# can-rs232.net
KiCad netlist of a schematic drawn in Altium Designer
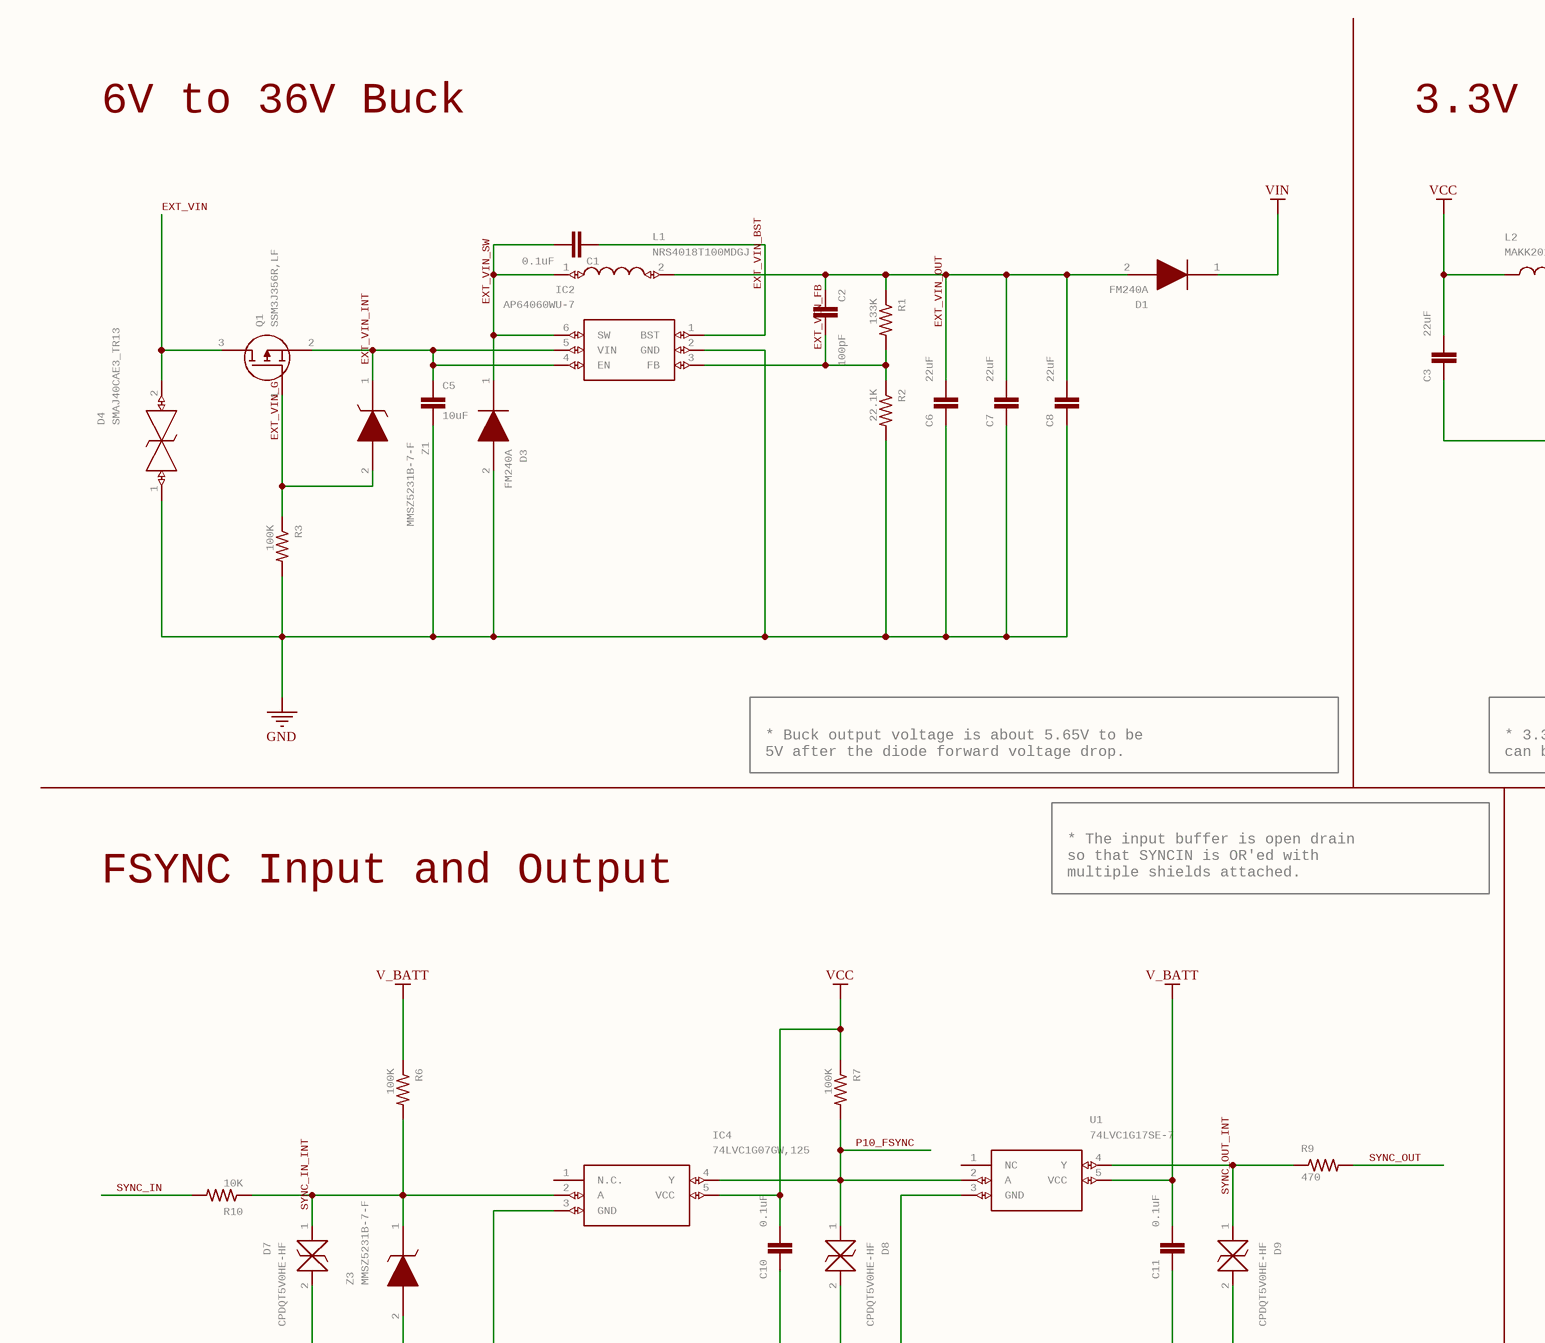
[diagram p0: can-rs232.SchDoc, top left]
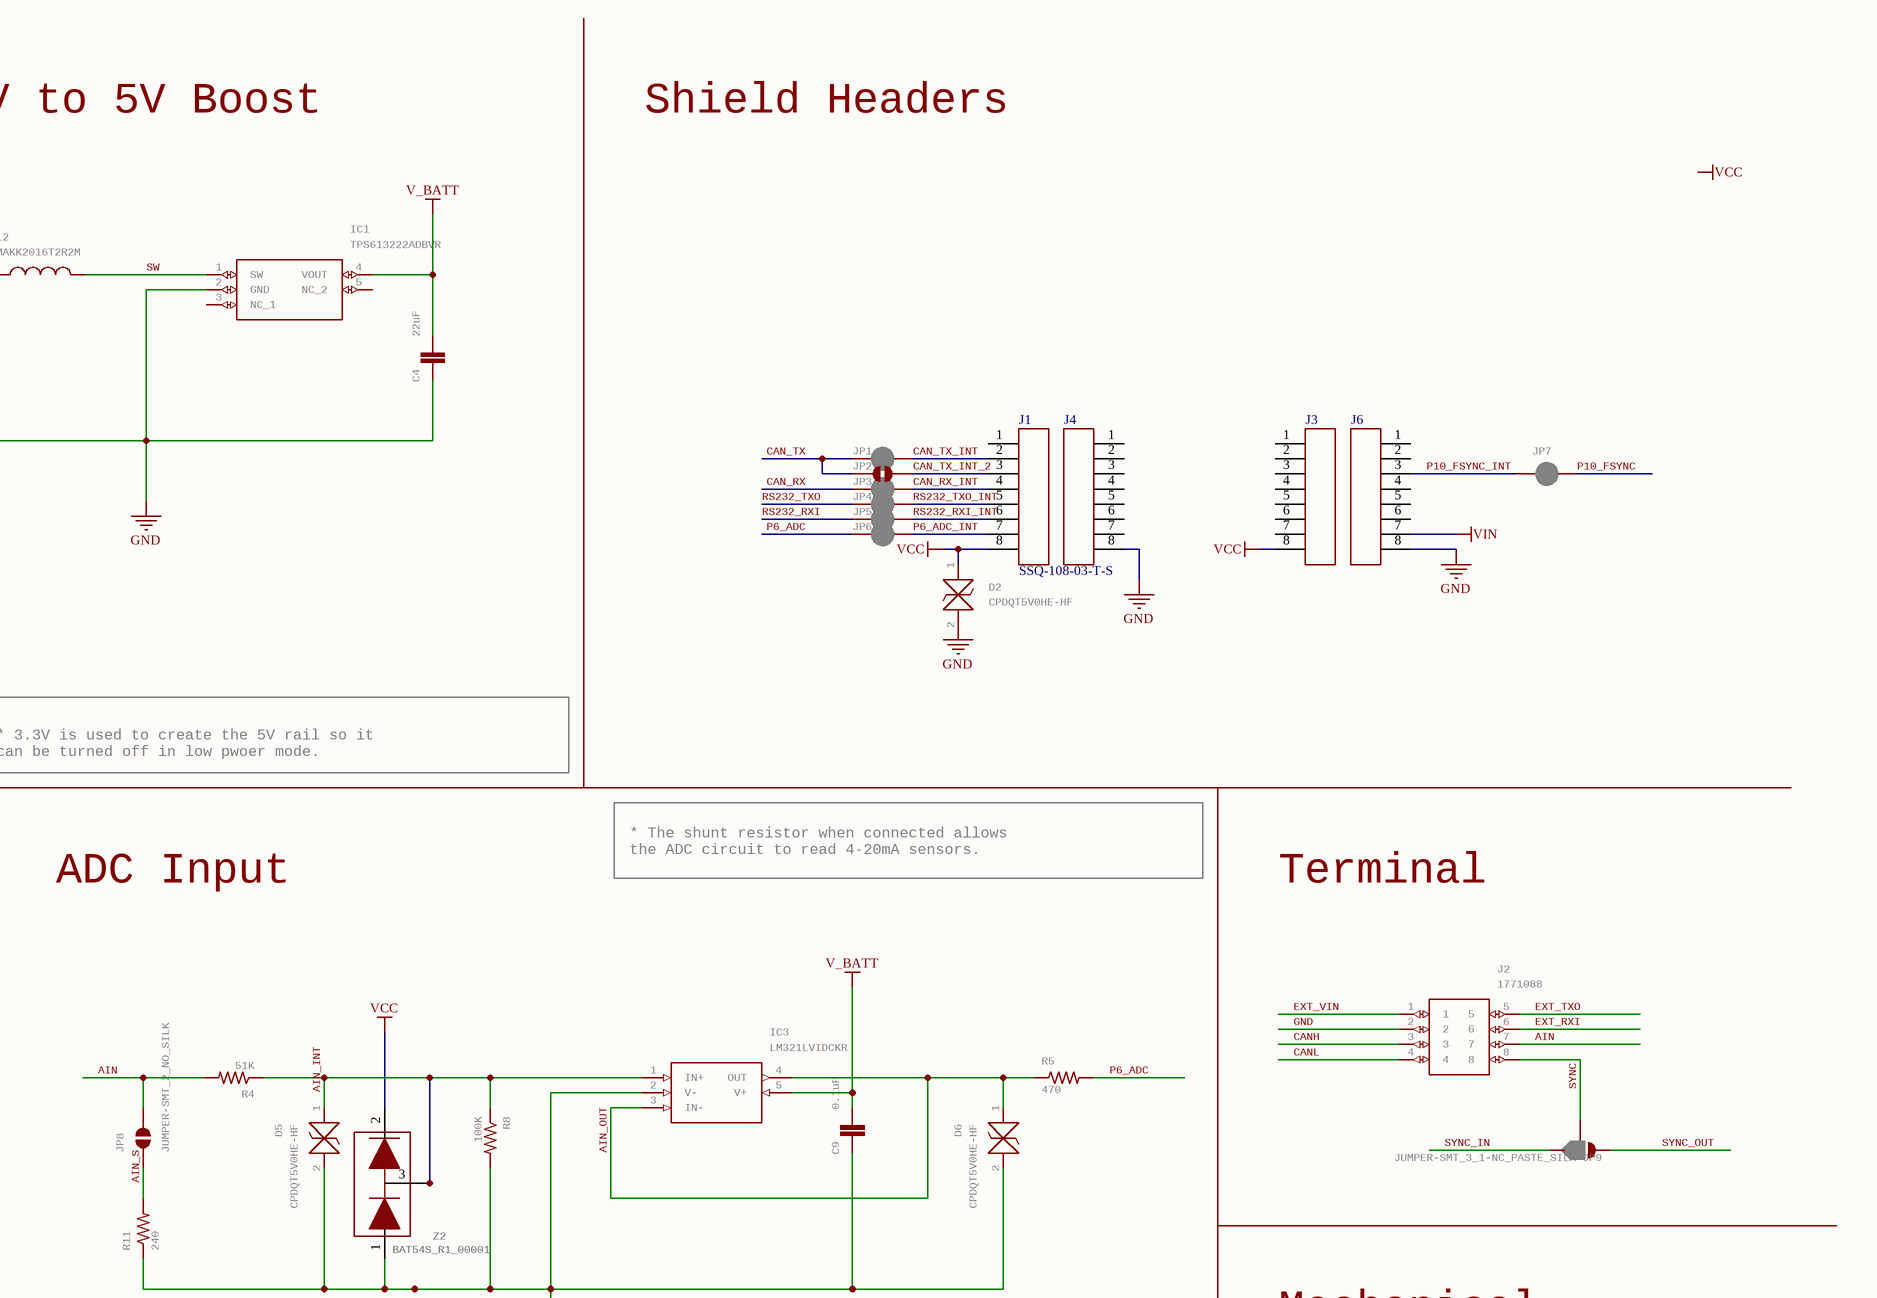
[diagram p1: can-rs232.SchDoc, top right]
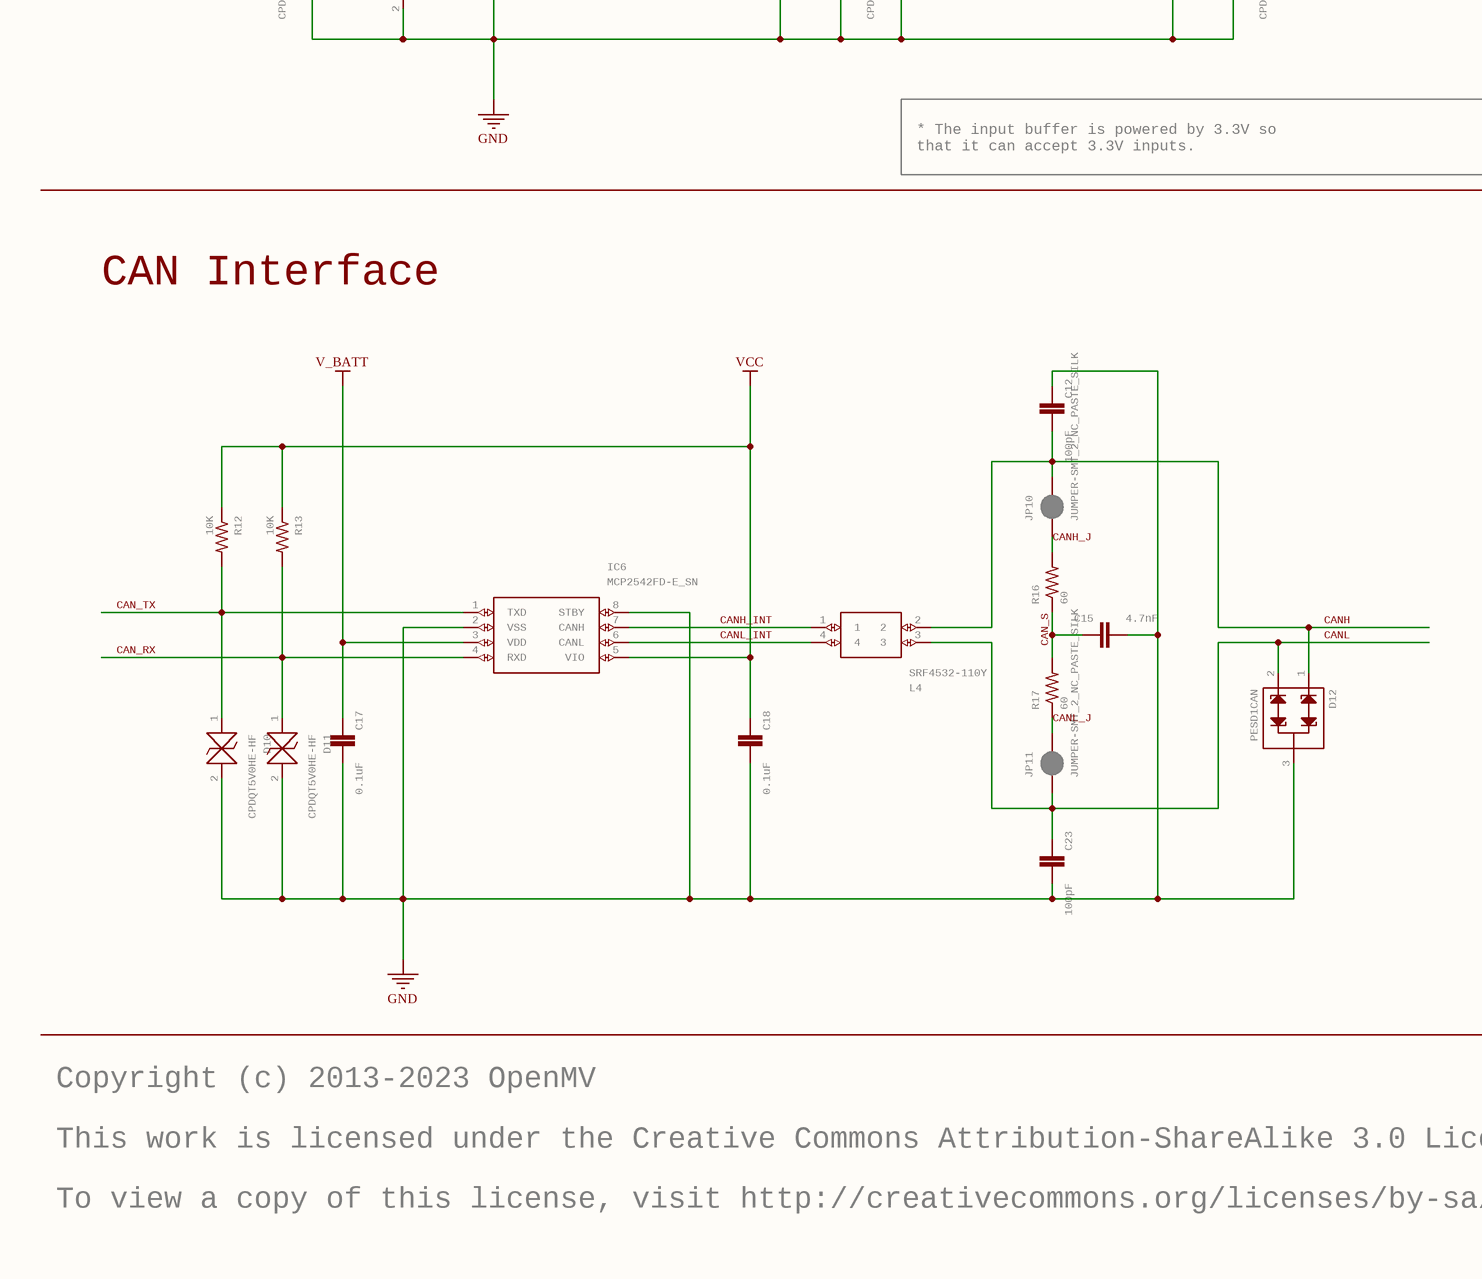
[diagram p2: can-rs232.SchDoc, bottom left]
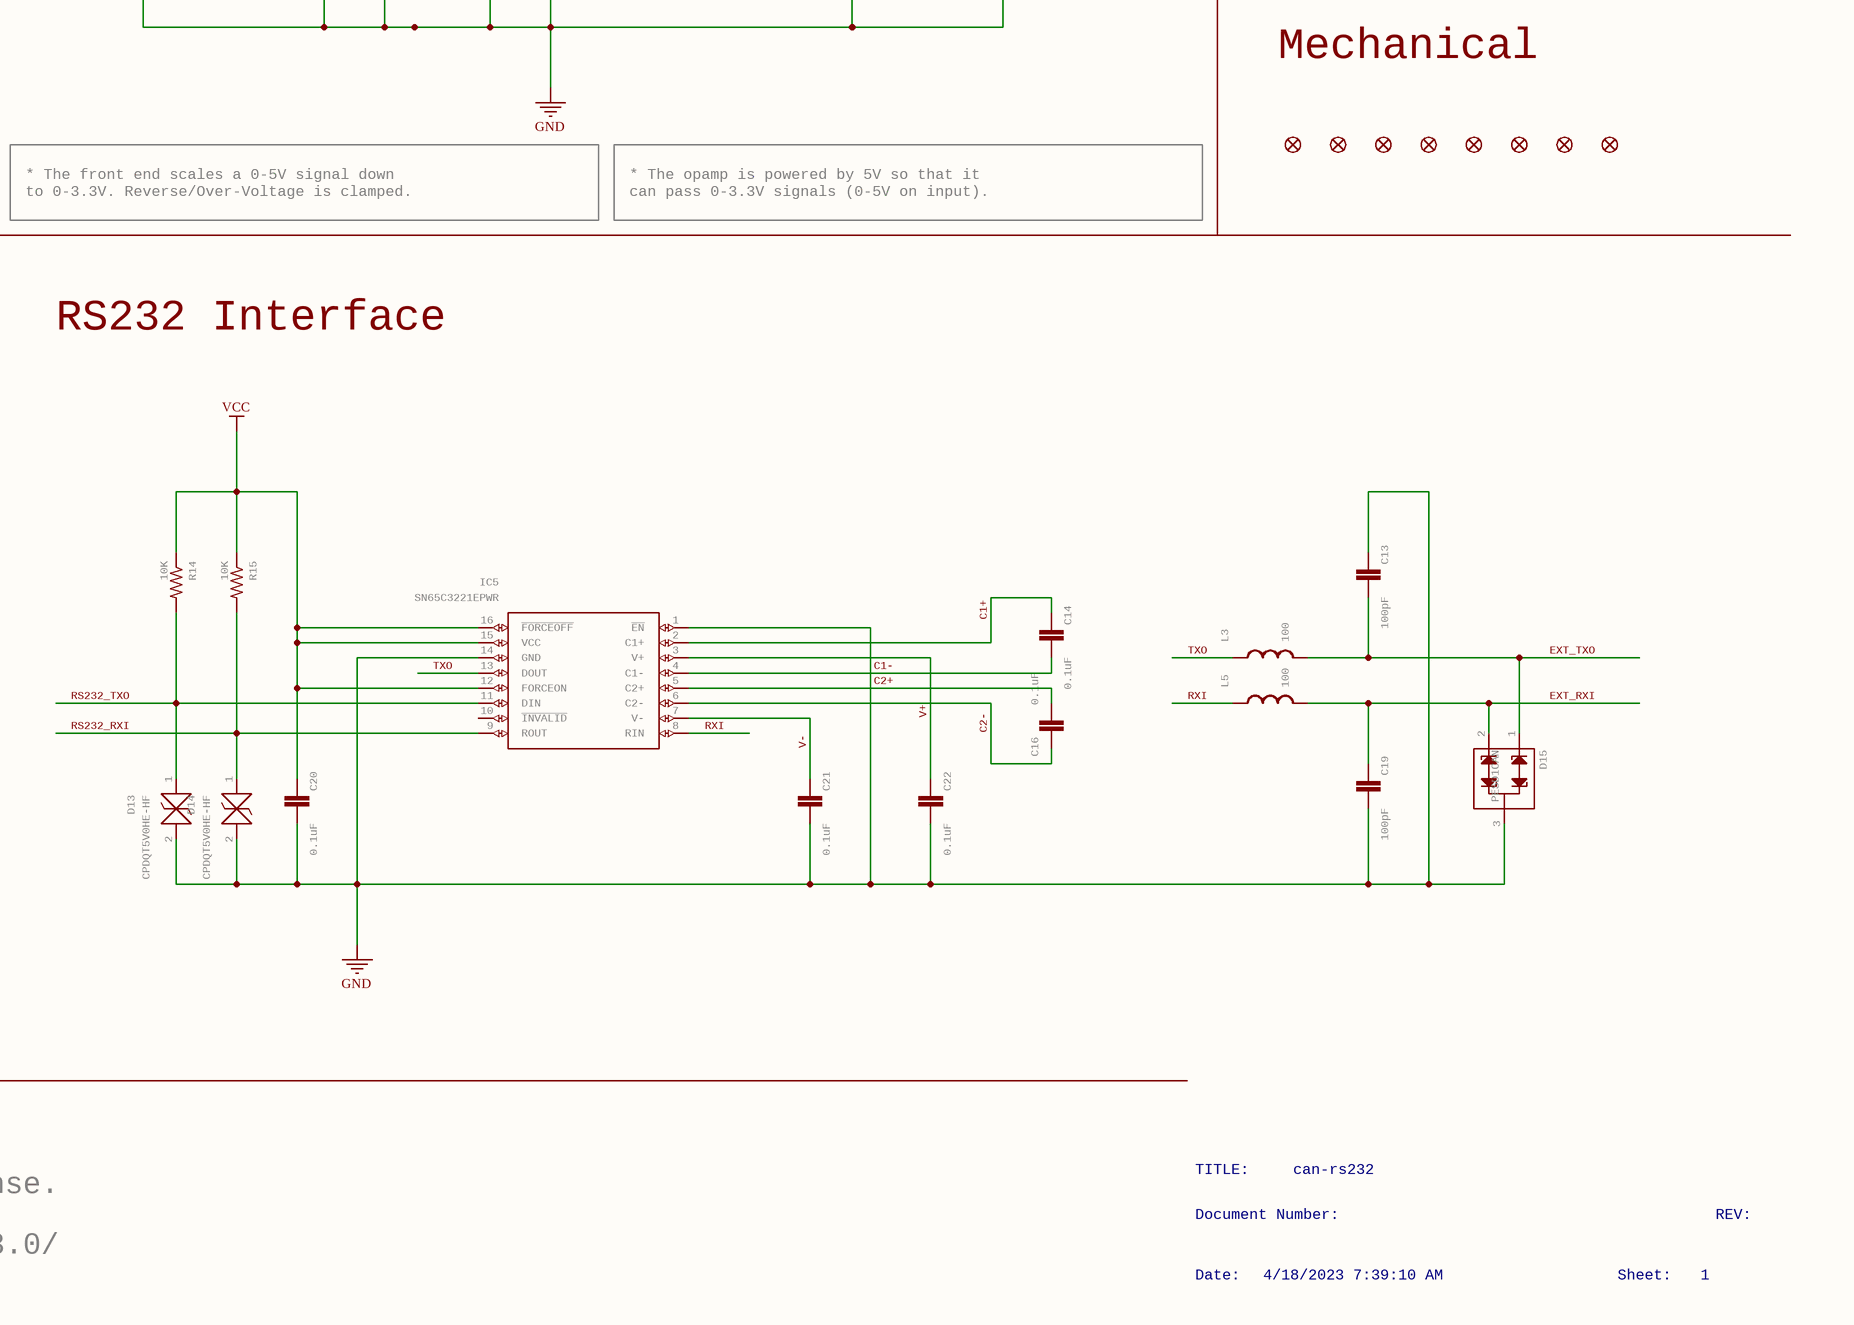
[diagram p3: can-rs232.SchDoc, bottom right]

(export (version "E")
  (design (tool "Eeschema 10.0.6"))
  (components
    (comp (ref "C1")
      (value "0.1uF")
      (footprint "0402-CAP")
      (description "CapacitorStandard 0603 ceramic capacitor, and 0.1\" leaded capacitor.")
      (fields (field (name "MPN") "GRM155R71H104KE14D"))
      (libsource (lib "") (part "CAP0402-CAP_2"))
    )
    (comp (ref "C2")
      (value "100pF")
      (footprint "0402-CAP")
      (description "CapacitorStandard 0603 ceramic capacitor, and 0.1\" leaded capacitor.")
      (fields (field (name "MPN") "CC0402JRNPO9BN101"))
      (libsource (lib "can-rs232") (part "CAP0402-CAP"))
    )
    (comp (ref "C3")
      (value "22uF")
      (footprint "0805")
      (fields (field (name "MPN") "CL21A226MQQNNNE"))
      (libsource (lib "can-rs232") (part "22UF-0805-6.3V-20%"))
    )
    (comp (ref "C4")
      (value "22uF")
      (footprint "0805")
      (fields (field (name "MPN") "CL21A226MQQNNNE"))
      (libsource (lib "can-rs232") (part "22UF-0805-6.3V-20%"))
    )
    (comp (ref "C5")
      (value "10uF")
      (footprint "C0805")
      (description "CAPACITOR, European symbol")
      (fields (field (name "MPN") "GRM21BR61H106KE43K"))
      (libsource (lib "can-rs232") (part "C-EUC0805"))
    )
    (comp (ref "C6")
      (value "22uF")
      (footprint "0805")
      (fields (field (name "MPN") "CL21A226MQQNNNE"))
      (libsource (lib "can-rs232") (part "22UF-0805-6.3V-20%"))
    )
    (comp (ref "C7")
      (value "22uF")
      (footprint "0805")
      (fields (field (name "MPN") "CL21A226MQQNNNE"))
      (libsource (lib "can-rs232") (part "22UF-0805-6.3V-20%"))
    )
    (comp (ref "C8")
      (value "22uF")
      (footprint "0805")
      (fields (field (name "MPN") "CL21A226MQQNNNE"))
      (libsource (lib "can-rs232") (part "22UF-0805-6.3V-20%"))
    )
    (comp (ref "C9")
      (value "0.1uF")
      (footprint "0402-CAP")
      (description "CapacitorStandard 0603 ceramic capacitor, and 0.1\" leaded capacitor.")
      (fields (field (name "MPN") "GRM155R71H104KE14D"))
      (libsource (lib "") (part "CAP0402-CAP_1"))
    )
    (comp (ref "C10")
      (value "0.1uF")
      (footprint "0402-CAP")
      (description "CapacitorStandard 0603 ceramic capacitor, and 0.1\" leaded capacitor.")
      (fields (field (name "MPN") "GRM155R71H104KE14D"))
      (libsource (lib "") (part "CAP0402-CAP_1"))
    )
    (comp (ref "C11")
      (value "0.1uF")
      (footprint "0402-CAP")
      (description "CapacitorStandard 0603 ceramic capacitor, and 0.1\" leaded capacitor.")
      (fields (field (name "MPN") "GRM155R71H104KE14D"))
      (libsource (lib "") (part "CAP0402-CAP_1"))
    )
    (comp (ref "C12")
      (value "100pF")
      (footprint "0402-CAP")
      (description "CapacitorStandard 0603 ceramic capacitor, and 0.1\" leaded capacitor.")
      (fields (field (name "MPN") "CC0402JRNPO9BN101"))
      (libsource (lib "can-rs232") (part "CAP0402-CAP"))
    )
    (comp (ref "C13")
      (value "100pF")
      (footprint "0402-CAP")
      (description "CapacitorStandard 0603 ceramic capacitor, and 0.1\" leaded capacitor.")
      (fields (field (name "MPN") "CC0402JRNPO9BN101"))
      (libsource (lib "can-rs232") (part "CAP0402-CAP"))
    )
    (comp (ref "C14")
      (value "0.1uF")
      (footprint "0402-CAP")
      (description "CapacitorStandard 0603 ceramic capacitor, and 0.1\" leaded capacitor.")
      (fields (field (name "MPN") "GRM155R71H104KE14D"))
      (libsource (lib "can-rs232") (part "CAP0402-CAP"))
    )
    (comp (ref "C15")
      (value "4.7nF")
      (footprint "0402-CAP")
      (description "CapacitorStandard 0603 ceramic capacitor, and 0.1\" leaded capacitor.")
      (fields (field (name "MPN") "GRM155R71H472JA01D"))
      (libsource (lib "") (part "CAP0402-CAP_3"))
    )
    (comp (ref "C16")
      (value "0.1uF")
      (footprint "0402-CAP")
      (description "CapacitorStandard 0603 ceramic capacitor, and 0.1\" leaded capacitor.")
      (fields (field (name "MPN") "GRM155R71H104KE14D"))
      (libsource (lib "") (part "CAP0402-CAP_1"))
    )
    (comp (ref "C17")
      (value "0.1uF")
      (footprint "0402-CAP")
      (description "CapacitorStandard 0603 ceramic capacitor, and 0.1\" leaded capacitor.")
      (fields (field (name "MPN") "GRM155R71H104KE14D"))
      (libsource (lib "can-rs232") (part "CAP0402-CAP"))
    )
    (comp (ref "C18")
      (value "0.1uF")
      (footprint "0402-CAP")
      (description "CapacitorStandard 0603 ceramic capacitor, and 0.1\" leaded capacitor.")
      (fields (field (name "MPN") "GRM155R71H104KE14D"))
      (libsource (lib "can-rs232") (part "CAP0402-CAP"))
    )
    (comp (ref "C19")
      (value "100pF")
      (footprint "0402-CAP")
      (description "CapacitorStandard 0603 ceramic capacitor, and 0.1\" leaded capacitor.")
      (fields (field (name "MPN") "CC0402JRNPO9BN101"))
      (libsource (lib "can-rs232") (part "CAP0402-CAP"))
    )
    (comp (ref "C20")
      (value "0.1uF")
      (footprint "0402-CAP")
      (description "CapacitorStandard 0603 ceramic capacitor, and 0.1\" leaded capacitor.")
      (fields (field (name "MPN") "GRM155R71H104KE14D"))
      (libsource (lib "can-rs232") (part "CAP0402-CAP"))
    )
    (comp (ref "C21")
      (value "0.1uF")
      (footprint "0402-CAP")
      (description "CapacitorStandard 0603 ceramic capacitor, and 0.1\" leaded capacitor.")
      (fields (field (name "MPN") "GRM155R71H104KE14D"))
      (libsource (lib "can-rs232") (part "CAP0402-CAP"))
    )
    (comp (ref "C22")
      (value "0.1uF")
      (footprint "0402-CAP")
      (description "CapacitorStandard 0603 ceramic capacitor, and 0.1\" leaded capacitor.")
      (fields (field (name "MPN") "GRM155R71H104KE14D"))
      (libsource (lib "can-rs232") (part "CAP0402-CAP"))
    )
    (comp (ref "C23")
      (value "100pF")
      (footprint "0402-CAP")
      (description "CapacitorStandard 0603 ceramic capacitor, and 0.1\" leaded capacitor.")
      (fields (field (name "MPN") "CC0402JRNPO9BN101"))
      (libsource (lib "can-rs232") (part "CAP0402-CAP"))
    )
    (comp (ref "D1")
      (value "FM240A")
      (footprint "DIOM5025X231N")
      (description "Diodes - General Purpose, Power, Switching GP Si Rectifier SMB,2A,40V   Source:  Datasheet")
      (fields (field (name "MOUSER_PART_NUMBER") "583-FM240A"))
      (libsource (lib "can-rs232") (part "FM240A"))
    )
    (comp (ref "D2")
      (value "CPDQT5V0HE-HF")
      (footprint "CPDQT5V0HEHF")
      (description "ESD Suppressors / TVS Diodes DIODE ESD 5VWM 65W 0402/SOD-923F   Source:  Datasheet")
      (fields (field (name "MOUSER_PART_NUMBER") "MOUSER_PART_NUMBER"))
      (libsource (lib "can-rs232") (part "CPDQT5V0HE-HF"))
    )
    (comp (ref "D3")
      (value "FM240A")
      (footprint "DIOM5025X231N")
      (description "Diodes - General Purpose, Power, Switching GP Si Rectifier SMB,2A,40V   Source:  Datasheet")
      (fields (field (name "MOUSER_PART_NUMBER") "583-FM240A"))
      (libsource (lib "can-rs232") (part "FM240A"))
    )
    (comp (ref "D4")
      (value "SMAJ40CAE3_TR13")
      (footprint "SMAJ40CAE3TR13")
      (description "ESD Suppressors / TVS Diodes TVS   Source:  Datasheet")
      (fields
        (field (name "MANUFACTURER_PART_NUMBER") "SMAJ40CAe3/TR13")
        (field (name "MOUSER_PART_NUMBER") "494-SMAJ40CAE3/TR13")
      )
      (libsource (lib "can-rs232") (part "SMAJ40CAE3_TR13"))
    )
    (comp (ref "D5")
      (value "CPDQT5V0HE-HF")
      (footprint "CPDQT5V0HEHF")
      (description "ESD Suppressors / TVS Diodes DIODE ESD 5VWM 65W 0402/SOD-923F   Source:  Datasheet")
      (fields (field (name "MOUSER_PART_NUMBER") "MOUSER_PART_NUMBER"))
      (libsource (lib "can-rs232") (part "CPDQT5V0HE-HF"))
    )
    (comp (ref "D6")
      (value "CPDQT5V0HE-HF")
      (footprint "CPDQT5V0HEHF")
      (description "ESD Suppressors / TVS Diodes DIODE ESD 5VWM 65W 0402/SOD-923F   Source:  Datasheet")
      (fields (field (name "MOUSER_PART_NUMBER") "MOUSER_PART_NUMBER"))
      (libsource (lib "can-rs232") (part "CPDQT5V0HE-HF"))
    )
    (comp (ref "D7")
      (value "CPDQT5V0HE-HF")
      (footprint "CPDQT5V0HEHF")
      (description "ESD Suppressors / TVS Diodes DIODE ESD 5VWM 65W 0402/SOD-923F   Source:  Datasheet")
      (fields (field (name "MOUSER_PART_NUMBER") "MOUSER_PART_NUMBER"))
      (libsource (lib "can-rs232") (part "CPDQT5V0HE-HF"))
    )
    (comp (ref "D8")
      (value "CPDQT5V0HE-HF")
      (footprint "CPDQT5V0HEHF")
      (description "ESD Suppressors / TVS Diodes DIODE ESD 5VWM 65W 0402/SOD-923F   Source:  Datasheet")
      (fields (field (name "MOUSER_PART_NUMBER") "MOUSER_PART_NUMBER"))
      (libsource (lib "can-rs232") (part "CPDQT5V0HE-HF"))
    )
    (comp (ref "D9")
      (value "CPDQT5V0HE-HF")
      (footprint "CPDQT5V0HEHF")
      (description "ESD Suppressors / TVS Diodes DIODE ESD 5VWM 65W 0402/SOD-923F   Source:  Datasheet")
      (fields (field (name "MOUSER_PART_NUMBER") "MOUSER_PART_NUMBER"))
      (libsource (lib "can-rs232") (part "CPDQT5V0HE-HF"))
    )
    (comp (ref "D10")
      (value "CPDQT5V0HE-HF")
      (footprint "CPDQT5V0HEHF")
      (description "ESD Suppressors / TVS Diodes DIODE ESD 5VWM 65W 0402/SOD-923F   Source:  Datasheet")
      (fields (field (name "MOUSER_PART_NUMBER") "MOUSER_PART_NUMBER"))
      (libsource (lib "can-rs232") (part "CPDQT5V0HE-HF"))
    )
    (comp (ref "D11")
      (value "CPDQT5V0HE-HF")
      (footprint "CPDQT5V0HEHF")
      (description "ESD Suppressors / TVS Diodes DIODE ESD 5VWM 65W 0402/SOD-923F   Source:  Datasheet")
      (fields (field (name "MOUSER_PART_NUMBER") "MOUSER_PART_NUMBER"))
      (libsource (lib "can-rs232") (part "CPDQT5V0HE-HF"))
    )
    (comp (ref "D12")
      (value "PESD1CAN")
      (footprint "SOT23-3")
      (fields (field (name "MPN") "VCAN36A2-03S-E3-08"))
      (libsource (lib "can-rs232") (part "PESD1CAN"))
    )
    (comp (ref "D13")
      (value "CPDQT5V0HE-HF")
      (footprint "CPDQT5V0HEHF")
      (description "ESD Suppressors / TVS Diodes DIODE ESD 5VWM 65W 0402/SOD-923F   Source:  Datasheet")
      (fields (field (name "MOUSER_PART_NUMBER") "MOUSER_PART_NUMBER"))
      (libsource (lib "can-rs232") (part "CPDQT5V0HE-HF"))
    )
    (comp (ref "D14")
      (value "CPDQT5V0HE-HF")
      (footprint "CPDQT5V0HEHF")
      (description "ESD Suppressors / TVS Diodes DIODE ESD 5VWM 65W 0402/SOD-923F   Source:  Datasheet")
      (fields (field (name "MOUSER_PART_NUMBER") "MOUSER_PART_NUMBER"))
      (libsource (lib "can-rs232") (part "CPDQT5V0HE-HF"))
    )
    (comp (ref "D15")
      (value "PESD1CAN")
      (footprint "SOT23-3")
      (fields (field (name "MPN") "VCAN36A2-03S-E3-08"))
      (libsource (lib "can-rs232") (part "PESD1CAN"))
    )
    (comp (ref "FD1")
      (value "FIDUCIAL1X2")
      (footprint "FIDUCIAL-1X2")
      (fields (field (name "LIBRARYNAME") "SparkFun-Aesthetics"))
      (libsource (lib "can-rs232") (part "FIDUCIAL1X2"))
    )
    (comp (ref "FD2")
      (value "FIDUCIAL1X2")
      (footprint "FIDUCIAL-1X2")
      (fields (field (name "LIBRARYNAME") "SparkFun-Aesthetics"))
      (libsource (lib "can-rs232") (part "FIDUCIAL1X2"))
    )
    (comp (ref "FD3")
      (value "FIDUCIAL1X2")
      (footprint "FIDUCIAL-1X2")
      (fields (field (name "LIBRARYNAME") "SparkFun-Aesthetics"))
      (libsource (lib "can-rs232") (part "FIDUCIAL1X2"))
    )
    (comp (ref "FD4")
      (value "FIDUCIAL1X2")
      (footprint "FIDUCIAL-1X2")
      (fields (field (name "LIBRARYNAME") "SparkFun-Aesthetics"))
      (libsource (lib "can-rs232") (part "FIDUCIAL1X2"))
    )
    (comp (ref "FD5")
      (value "FIDUCIAL1X2")
      (footprint "FIDUCIAL-1X2")
      (fields (field (name "LIBRARYNAME") "SparkFun-Aesthetics"))
      (libsource (lib "can-rs232") (part "FIDUCIAL1X2"))
    )
    (comp (ref "FD6")
      (value "FIDUCIAL1X2")
      (footprint "FIDUCIAL-1X2")
      (fields (field (name "LIBRARYNAME") "SparkFun-Aesthetics"))
      (libsource (lib "can-rs232") (part "FIDUCIAL1X2"))
    )
    (comp (ref "FD7")
      (value "FIDUCIAL1X2")
      (footprint "FIDUCIAL-1X2")
      (fields (field (name "LIBRARYNAME") "SparkFun-Aesthetics"))
      (libsource (lib "can-rs232") (part "FIDUCIAL1X2"))
    )
    (comp (ref "FD8")
      (value "FIDUCIAL1X2")
      (footprint "FIDUCIAL-1X2")
      (fields (field (name "LIBRARYNAME") "SparkFun-Aesthetics"))
      (libsource (lib "can-rs232") (part "FIDUCIAL1X2"))
    )
    (comp (ref "IC1")
      (value "TPS613222ADBVR")
      (footprint "SOT95P280X145-5N")
      (description "6-uA Quiescent Current, 1.8-A Switch Current Boost Converter   Source:  Datasheet")
      (fields (field (name "MOUSER_PART_NUMBER") "595-TPS613222ADBVR"))
      (libsource (lib "can-rs232") (part "TPS613222ADBVR"))
    )
    (comp (ref "IC2")
      (value "AP64060WU-7")
      (footprint "SOT95P280X100-6N")
      (description "Switching Voltage Regulators DCDC Conv HV Buck TSOT26(STD) T&R 3K   Source:  Datasheet")
      (fields (field (name "MOUSER_PART_NUMBER") "621-AP64060WU-7"))
      (libsource (lib "can-rs232") (part "AP64060WU-7"))
    )
    (comp (ref "IC3")
      (value "LM321LVIDCKR")
      (footprint "SOT65P210X110-5N")
      (description "1-Channel industry standard low voltage operational amplifier   Source:  Datasheet")
      (fields (field (name "MOUSER_PART_NUMBER") "595-LM321LVIDCKR"))
      (libsource (lib "can-rs232") (part "LM321LVIDCKR"))
    )
    (comp (ref "IC4")
      (value "74LVC1G07GW,125")
      (footprint "SOT65P212X110-5N")
      (description "74LVC1G07 - Buffer with open-drain output@en-us   Source:  Datasheet")
      (fields (field (name "MOUSER_PART_NUMBER") "771-74LVC1G07GW-G"))
      (libsource (lib "can-rs232") (part "74LVC1G07GW,125"))
    )
    (comp (ref "IC5")
      (value "SN65C3221EPWR")
      (footprint "SOP65P640X120-16N")
      (description "3-V To 5.5-V Single Channel RS-232 1 Mbit/s Line Driver/Receiver   Source:  Datasheet")
      (fields (field (name "MOUSER_PART_NUMBER") "595-SN65C3221EPWR"))
      (libsource (lib "can-rs232") (part "SN65C3221EPWR"))
    )
    (comp (ref "IC6")
      (value "MCP2542FD-E_SN")
      (footprint "SOIC127P600X175-8N")
      (fields
        (field (name "MANUFACTURER_PART_NUMBER") "MCP2542FD-E/SN")
        (field (name "MOUSER_PART_NUMBER") "579-MCP2542FD-E/SN")
      )
      (libsource (lib "can-rs232") (part "MCP2542FD-E_SN"))
    )
    (comp (ref "J1") (value "SSQ-108-03-T-S") (footprint "HDR_1X8") (libsource (lib "pir") (part "HDR_1X8")))
    (comp (ref "J2")
      (value "1771088")
      (footprint "1771088")
      (fields (field (name "MOUSER_PART_NUMBER") "651-1771088"))
      (libsource (lib "can-rs232") (part "1771088"))
    )
    (comp (ref "J3") (value "SSQ-108-03-T-S") (footprint "HDR_1X8") (libsource (lib "pir") (part "HDR_1X8")))
    (comp (ref "J4") (value "SSQ-108-03-T-S") (footprint "HDR_1X8") (libsource (lib "") (part "HDR_1X8_1")))
    (comp (ref "J6") (value "SSQ-108-03-T-S") (footprint "HDR_1X8") (libsource (lib "") (part "HDR_1X8_1")))
    (comp (ref "JP1")
      (value "JUMPER-SMT_2_NC_PASTE_SILK")
      (footprint "SMT-JUMPER_2_NC_PASTE_SILK")
      (libsource (lib "can-rs232") (part "JUMPER-SMT_2_NC_PASTE_SILK"))
    )
    (comp (ref "JP2")
      (value "JUMPER-SMT_2_NO_SILK")
      (footprint "SMT-JUMPER_2_NO_SILK")
      (libsource (lib "can-rs232") (part "JUMPER-SMT_2_NO_SILK"))
    )
    (comp (ref "JP3")
      (value "JUMPER-SMT_2_NC_PASTE_SILK")
      (footprint "SMT-JUMPER_2_NC_PASTE_SILK")
      (libsource (lib "can-rs232") (part "JUMPER-SMT_2_NC_PASTE_SILK"))
    )
    (comp (ref "JP4")
      (value "JUMPER-SMT_2_NC_PASTE_SILK")
      (footprint "SMT-JUMPER_2_NC_PASTE_SILK")
      (libsource (lib "can-rs232") (part "JUMPER-SMT_2_NC_PASTE_SILK"))
    )
    (comp (ref "JP5")
      (value "JUMPER-SMT_2_NC_PASTE_SILK")
      (footprint "SMT-JUMPER_2_NC_PASTE_SILK")
      (libsource (lib "can-rs232") (part "JUMPER-SMT_2_NC_PASTE_SILK"))
    )
    (comp (ref "JP6")
      (value "JUMPER-SMT_2_NC_PASTE_SILK")
      (footprint "SMT-JUMPER_2_NC_PASTE_SILK")
      (libsource (lib "can-rs232") (part "JUMPER-SMT_2_NC_PASTE_SILK"))
    )
    (comp (ref "JP7")
      (value "JUMPER-SMT_2_NC_PASTE_SILK")
      (footprint "SMT-JUMPER_2_NC_PASTE_SILK")
      (libsource (lib "can-rs232") (part "JUMPER-SMT_2_NC_PASTE_SILK"))
    )
    (comp (ref "JP8")
      (value "JUMPER-SMT_2_NO_SILK")
      (footprint "SMT-JUMPER_2_NO_SILK")
      (libsource (lib "can-rs232") (part "JUMPER-SMT_2_NO_SILK"))
    )
    (comp (ref "JP9")
      (value "JUMPER-SMT_3_1-NC_PASTE_SILK")
      (footprint "SMT-JUMPER_3_1-NC_PASTE_SILK")
      (libsource (lib "can-rs232") (part "JUMPER-SMT_3_1-NC_PASTE_SILK"))
    )
    (comp (ref "JP10")
      (value "JUMPER-SMT_2_NC_PASTE_SILK")
      (footprint "SMT-JUMPER_2_NC_PASTE_SILK")
      (libsource (lib "can-rs232") (part "JUMPER-SMT_2_NC_PASTE_SILK"))
    )
    (comp (ref "JP11")
      (value "JUMPER-SMT_2_NC_PASTE_SILK")
      (footprint "SMT-JUMPER_2_NC_PASTE_SILK")
      (libsource (lib "can-rs232") (part "JUMPER-SMT_2_NC_PASTE_SILK"))
    )
    (comp (ref "L1")
      (value "NRS4018T100MDGJ")
      (footprint "NRS4018T100MDGJ")
      (description "Fixed Inductors 4018 10uH 180mOhms +/-20%Tol 1200mA   Source:  Datasheet")
      (fields (field (name "MOUSER_PART_NUMBER") "963-NRS4018T100MDGJ"))
      (libsource (lib "can-rs232") (part "NRS4018T100MDGJ"))
    )
    (comp (ref "L2")
      (value "MAKK2016T2R2M")
      (footprint "INDC2016X100N")
      (description "INDUCTOR, METAL CORE Check availability")
      (fields (field (name "MF") "Taiyo Yuden"))
      (libsource (lib "can-rs232") (part "MAKK2016T2R2M"))
    )
    (comp (ref "L3")
      (value "100")
      (footprint "C0402")
      (fields (field (name "MPN") "MFBM1V1005-101-R"))
      (libsource (lib "can-rs232") (part "INDUCTOR0402"))
    )
    (comp (ref "L4")
      (value "SRF4532-110Y")
      (footprint "SRF4532101Y")
      (fields (field (name "MOUSER_PART_NUMBER") "652-SRF4532-110Y"))
      (libsource (lib "can-rs232") (part "SRF4532-110Y"))
    )
    (comp (ref "L5")
      (value "100")
      (footprint "C0402")
      (fields (field (name "MPN") "MFBM1V1005-101-R"))
      (libsource (lib "can-rs232") (part "INDUCTOR0402"))
    )
    (comp (ref "Q1")
      (value "SSM3J356R,LF")
      (footprint "SOTFL95P240X88-3N")
      (description "MOSFET Small-signal MOSFET ID: -2A, VDSS: -60V   Source:  Datasheet")
      (fields (field (name "MOUSER_PART_NUMBER") "757-SSM3J356RLF"))
      (libsource (lib "can-rs232") (part "SSM3J356R,LF"))
    )
    (comp (ref "R1")
      (value "133K")
      (footprint "0402-RES")
      (description "ResistorBasic schematic elements and footprints for 0603, 1206, and PTH resistors.")
      (fields (field (name "MPN") "RC0402FR-07133KL"))
      (libsource (lib "can-rs232") (part "RESISTOR0402-RES"))
    )
    (comp (ref "R2")
      (value "22.1K")
      (footprint "0402-RES")
      (description "ResistorBasic schematic elements and footprints for 0603, 1206, and PTH resistors.")
      (fields (field (name "MPN") "CR0402-FX-2212GLF"))
      (libsource (lib "can-rs232") (part "RESISTOR0402-RES"))
    )
    (comp (ref "R3")
      (value "100K")
      (footprint "0402-RES")
      (description "ResistorBasic schematic elements and footprints for 0603, 1206, and PTH resistors.")
      (fields (field (name "MPN") "AC0402FR-07100KL"))
      (libsource (lib "can-rs232") (part "RESISTOR0402-RES"))
    )
    (comp (ref "R4")
      (value "51K")
      (footprint "0402-RES")
      (description "ResistorBasic schematic elements and footprints for 0603, 1206, and PTH resistors.")
      (fields (field (name "MPN") "RC0402JR-0751KL"))
      (libsource (lib "can-rs232") (part "RESISTOR0402-RES"))
    )
    (comp (ref "R5")
      (value "470")
      (footprint "R0603")
      (description "RESISTOR, American symbol")
      (fields (field (name "MPN") "CR0603-FX-4700ELF"))
      (libsource (lib "can-rs232") (part "R-US_R0603"))
    )
    (comp (ref "R6")
      (value "100K")
      (footprint "0402-RES")
      (description "ResistorBasic schematic elements and footprints for 0603, 1206, and PTH resistors.")
      (fields (field (name "MPN") "AC0402FR-07100KL"))
      (libsource (lib "can-rs232") (part "RESISTOR0402-RES"))
    )
    (comp (ref "R7")
      (value "100K")
      (footprint "0402-RES")
      (description "ResistorBasic schematic elements and footprints for 0603, 1206, and PTH resistors.")
      (fields (field (name "MPN") "AC0402FR-07100KL"))
      (libsource (lib "can-rs232") (part "RESISTOR0402-RES"))
    )
    (comp (ref "R8")
      (value "100K")
      (footprint "0402-RES")
      (description "ResistorBasic schematic elements and footprints for 0603, 1206, and PTH resistors.")
      (fields (field (name "MPN") "AC0402FR-07100KL"))
      (libsource (lib "can-rs232") (part "RESISTOR0402-RES"))
    )
    (comp (ref "R9")
      (value "470")
      (footprint "R0603")
      (description "RESISTOR, American symbol")
      (fields (field (name "MPN") "CR0603-FX-4700ELF"))
      (libsource (lib "can-rs232") (part "R-US_R0603"))
    )
    (comp (ref "R10")
      (value "10K")
      (footprint "0402-RES")
      (description "ResistorBasic schematic elements and footprints for 0603, 1206, and PTH resistors.")
      (fields (field (name "MPN") "AC0402FR-1310KL"))
      (libsource (lib "can-rs232") (part "RESISTOR0402-RES"))
    )
    (comp (ref "R11")
      (value "240")
      (footprint "R0603")
      (description "RESISTOR, American symbol")
      (fields (field (name "MPN") "RK73B1JTTD241J"))
      (libsource (lib "can-rs232") (part "R-US_R0603"))
    )
    (comp (ref "R12")
      (value "10K")
      (footprint "0402-RES")
      (description "ResistorBasic schematic elements and footprints for 0603, 1206, and PTH resistors.")
      (fields (field (name "MPN") "AC0402FR-1310KL"))
      (libsource (lib "can-rs232") (part "RESISTOR0402-RES"))
    )
    (comp (ref "R13")
      (value "10K")
      (footprint "0402-RES")
      (description "ResistorBasic schematic elements and footprints for 0603, 1206, and PTH resistors.")
      (fields (field (name "MPN") "AC0402FR-1310KL"))
      (libsource (lib "can-rs232") (part "RESISTOR0402-RES"))
    )
    (comp (ref "R14")
      (value "10K")
      (footprint "0402-RES")
      (description "ResistorBasic schematic elements and footprints for 0603, 1206, and PTH resistors.")
      (fields (field (name "MPN") "AC0402FR-1310KL"))
      (libsource (lib "can-rs232") (part "RESISTOR0402-RES"))
    )
    (comp (ref "R15")
      (value "10K")
      (footprint "0402-RES")
      (description "ResistorBasic schematic elements and footprints for 0603, 1206, and PTH resistors.")
      (fields (field (name "MPN") "AC0402FR-1310KL"))
      (libsource (lib "can-rs232") (part "RESISTOR0402-RES"))
    )
    (comp (ref "R16")
      (value "60")
      (footprint "R1206")
      (description "RESISTOR, American symbol")
      (fields (field (name "MPN") "RC1206FR-0760R4L"))
      (libsource (lib "can-rs232") (part "R-US_R1206"))
    )
    (comp (ref "R17")
      (value "60")
      (footprint "R1206")
      (description "RESISTOR, American symbol")
      (fields (field (name "MPN") "RC1206FR-0760R4L"))
      (libsource (lib "can-rs232") (part "R-US_R1206"))
    )
    (comp (ref "U1")
      (value "74LVC1G17SE-7")
      (footprint "SOT65P210X110-5N")
      (fields (field (name "MOUSER_PART_NUMBER") "621-74LVC1G17SE-7"))
      (libsource (lib "can-rs232") (part "74LVC1G17SE-7"))
    )
    (comp (ref "Z1")
      (value "MMSZ5231B-7-F")
      (footprint "SOD3716X145N")
      (fields (field (name "MOUSER_PART_NUMBER") "621-MMSZ5231B-F"))
      (libsource (lib "can-rs232") (part "MMSZ5231B-7-F"))
    )
    (comp (ref "Z2")
      (value "BAT54S_R1_00001")
      (footprint "SOT23-3")
      (libsource (lib "can-rs232") (part "BAT54S_R1_00001"))
    )
    (comp (ref "Z3")
      (value "MMSZ5231B-7-F")
      (footprint "SOD3716X145N")
      (fields (field (name "MOUSER_PART_NUMBER") "621-MMSZ5231B-F"))
      (libsource (lib "can-rs232") (part "MMSZ5231B-7-F"))
    )
  )
  (nets
    (net (code "1") (name "/AIN") (class "Default")
      (node (ref "J2") (pin "7") (pinfunction "7_7") (pintype "bidirectional"))
      (node (ref "JP8") (pin "2") (pinfunction "2_2") (pintype "passive"))
      (node (ref "R4") (pin "2") (pinfunction "2_2") (pintype "passive"))
    )
    (net (code "2") (name "/AIN_INT") (class "Default")
      (node (ref "D5") (pin "1") (pinfunction "1_1") (pintype "bidirectional"))
      (node (ref "IC3") (pin "1") (pinfunction "IN+_1") (pintype "input"))
      (node (ref "R4") (pin "1") (pinfunction "1_1") (pintype "passive"))
      (node (ref "R8") (pin "1") (pinfunction "1_1") (pintype "passive"))
      (node (ref "Z2") (pin "3") (pintype "passive"))
    )
    (net (code "3") (name "/AIN_OUT") (class "Default")
      (node (ref "D6") (pin "1") (pinfunction "1_1") (pintype "bidirectional"))
      (node (ref "IC3") (pin "3") (pinfunction "IN-_3") (pintype "input"))
      (node (ref "IC3") (pin "4") (pinfunction "OUT_4") (pintype "output"))
      (node (ref "R5") (pin "1") (pinfunction "1_1") (pintype "passive"))
    )
    (net (code "4") (name "/AIN_S") (class "Default")
      (node (ref "JP8") (pin "1") (pinfunction "1_1") (pintype "passive"))
      (node (ref "R11") (pin "2") (pinfunction "2_2") (pintype "passive"))
    )
    (net (code "5") (name "/C1+") (class "Default")
      (node (ref "C14") (pin "1") (pinfunction "1_1") (pintype "passive"))
      (node (ref "IC5") (pin "2") (pinfunction "C1+_2") (pintype "bidirectional"))
    )
    (net (code "6") (name "/C1-") (class "Default")
      (node (ref "C14") (pin "2") (pinfunction "2_2") (pintype "passive"))
      (node (ref "IC5") (pin "4") (pinfunction "C1-_4") (pintype "bidirectional"))
    )
    (net (code "7") (name "/C2+") (class "Default")
      (node (ref "C16") (pin "2") (pinfunction "2_2") (pintype "passive"))
      (node (ref "IC5") (pin "5") (pinfunction "C2+_5") (pintype "bidirectional"))
    )
    (net (code "8") (name "/C2-") (class "Default")
      (node (ref "C16") (pin "1") (pinfunction "1_1") (pintype "passive"))
      (node (ref "IC5") (pin "6") (pinfunction "C2-_6") (pintype "bidirectional"))
    )
    (net (code "9") (name "/CANH") (class "Default")
      (node (ref "C12") (pin "2") (pinfunction "2_2") (pintype "passive"))
      (node (ref "D12") (pin "1") (pinfunction "1_1") (pintype "bidirectional"))
      (node (ref "J2") (pin "3") (pinfunction "3_3") (pintype "bidirectional"))
      (node (ref "JP10") (pin "2") (pinfunction "2_2") (pintype "passive"))
      (node (ref "L4") (pin "2") (pinfunction "2_2") (pintype "bidirectional"))
    )
    (net (code "10") (name "/CANH_INT") (class "Default")
      (node (ref "IC6") (pin "7") (pinfunction "CANH_7") (pintype "bidirectional"))
      (node (ref "L4") (pin "1") (pinfunction "1_1") (pintype "bidirectional"))
    )
    (net (code "11") (name "/CANH_J") (class "Default")
      (node (ref "JP10") (pin "1") (pinfunction "1_1") (pintype "passive"))
      (node (ref "R16") (pin "2") (pinfunction "2_2") (pintype "passive"))
    )
    (net (code "12") (name "/CANL") (class "Default")
      (node (ref "C23") (pin "1") (pinfunction "1_1") (pintype "passive"))
      (node (ref "D12") (pin "2") (pinfunction "2_2") (pintype "bidirectional"))
      (node (ref "J2") (pin "4") (pinfunction "4_4") (pintype "bidirectional"))
      (node (ref "JP11") (pin "1") (pinfunction "1_1") (pintype "passive"))
      (node (ref "L4") (pin "3") (pinfunction "3_3") (pintype "bidirectional"))
    )
    (net (code "13") (name "/CANL_INT") (class "Default")
      (node (ref "IC6") (pin "6") (pinfunction "CANL_6") (pintype "bidirectional"))
      (node (ref "L4") (pin "4") (pinfunction "4_4") (pintype "bidirectional"))
    )
    (net (code "14") (name "/CANL_J") (class "Default")
      (node (ref "JP11") (pin "2") (pinfunction "2_2") (pintype "passive"))
      (node (ref "R17") (pin "1") (pinfunction "1_1") (pintype "passive"))
    )
    (net (code "15") (name "/CAN_RX") (class "Default")
      (node (ref "D11") (pin "1") (pinfunction "1_1") (pintype "bidirectional"))
      (node (ref "IC6") (pin "4") (pinfunction "RXD_4") (pintype "bidirectional"))
      (node (ref "JP3") (pin "1") (pinfunction "1_1") (pintype "passive"))
      (node (ref "R13") (pin "2") (pinfunction "2_2") (pintype "passive"))
    )
    (net (code "16") (name "/CAN_RX_INT") (class "Default")
      (node (ref "J1") (pin "4") (pintype "passive"))
      (node (ref "JP3") (pin "2") (pinfunction "2_2") (pintype "passive"))
    )
    (net (code "17") (name "/CAN_S") (class "Default")
      (node (ref "C15") (pin "1") (pinfunction "1_1") (pintype "passive"))
      (node (ref "R16") (pin "1") (pinfunction "1_1") (pintype "passive"))
      (node (ref "R17") (pin "2") (pinfunction "2_2") (pintype "passive"))
    )
    (net (code "18") (name "/CAN_TX") (class "Default")
      (node (ref "D10") (pin "1") (pinfunction "1_1") (pintype "bidirectional"))
      (node (ref "IC6") (pin "1") (pinfunction "TXD_1") (pintype "bidirectional"))
      (node (ref "JP1") (pin "2") (pinfunction "2_2") (pintype "passive"))
      (node (ref "JP2") (pin "2") (pinfunction "2_2") (pintype "passive"))
      (node (ref "R12") (pin "2") (pinfunction "2_2") (pintype "passive"))
    )
    (net (code "19") (name "/CAN_TX_INT") (class "Default")
      (node (ref "J1") (pin "2") (pintype "passive"))
      (node (ref "JP1") (pin "1") (pinfunction "1_1") (pintype "passive"))
    )
    (net (code "20") (name "/CAN_TX_INT_2") (class "Default")
      (node (ref "J1") (pin "3") (pintype "passive"))
      (node (ref "JP2") (pin "1") (pinfunction "1_1") (pintype "passive"))
    )
    (net (code "21") (name "/EXT_RXI") (class "Default")
      (node (ref "C19") (pin "1") (pinfunction "1_1") (pintype "passive"))
      (node (ref "D15") (pin "2") (pinfunction "2_2") (pintype "bidirectional"))
      (node (ref "J2") (pin "6") (pinfunction "6_6") (pintype "bidirectional"))
      (node (ref "L5") (pin "2") (pinfunction "2_2") (pintype "passive"))
    )
    (net (code "22") (name "/EXT_TXO") (class "Default")
      (node (ref "C13") (pin "2") (pinfunction "2_2") (pintype "passive"))
      (node (ref "D15") (pin "1") (pinfunction "1_1") (pintype "bidirectional"))
      (node (ref "J2") (pin "5") (pinfunction "5_5") (pintype "bidirectional"))
      (node (ref "L3") (pin "2") (pinfunction "2_2") (pintype "passive"))
    )
    (net (code "23") (name "/EXT_VIN") (class "Default")
      (node (ref "D4") (pin "2") (pinfunction "2_2") (pintype "bidirectional"))
      (node (ref "J2") (pin "1") (pinfunction "1_1") (pintype "bidirectional"))
      (node (ref "Q1") (pin "3") (pinfunction "D_3") (pintype "bidirectional"))
    )
    (net (code "24") (name "/EXT_VIN_BST") (class "Default")
      (node (ref "C1") (pin "1") (pinfunction "1_1") (pintype "passive"))
      (node (ref "IC2") (pin "1") (pinfunction "BST_1") (pintype "bidirectional"))
    )
    (net (code "25") (name "/EXT_VIN_FB") (class "Default")
      (node (ref "C2") (pin "2") (pinfunction "2_2") (pintype "passive"))
      (node (ref "IC2") (pin "3") (pinfunction "FB_3") (pintype "bidirectional"))
      (node (ref "R1") (pin "2") (pinfunction "2_2") (pintype "passive"))
      (node (ref "R2") (pin "1") (pinfunction "1_1") (pintype "passive"))
    )
    (net (code "26") (name "/EXT_VIN_G") (class "Default")
      (node (ref "Q1") (pin "1") (pinfunction "G_1") (pintype "bidirectional"))
      (node (ref "R3") (pin "1") (pinfunction "1_1") (pintype "passive"))
      (node (ref "Z1") (pin "2") (pinfunction "A_2") (pintype "bidirectional"))
    )
    (net (code "27") (name "/EXT_VIN_INT") (class "Default")
      (node (ref "C5") (pin "1") (pinfunction "1_1") (pintype "passive"))
      (node (ref "IC2") (pin "4") (pinfunction "EN_4") (pintype "bidirectional"))
      (node (ref "IC2") (pin "5") (pinfunction "VIN_5") (pintype "bidirectional"))
      (node (ref "Q1") (pin "2") (pinfunction "S_2") (pintype "bidirectional"))
      (node (ref "Z1") (pin "1") (pinfunction "K_1") (pintype "bidirectional"))
    )
    (net (code "28") (name "/EXT_VIN_OUT") (class "Default")
      (node (ref "C2") (pin "1") (pinfunction "1_1") (pintype "passive"))
      (node (ref "C6") (pin "2") (pinfunction "2_2") (pintype "passive"))
      (node (ref "C7") (pin "2") (pinfunction "2_2") (pintype "passive"))
      (node (ref "C8") (pin "2") (pinfunction "2_2") (pintype "passive"))
      (node (ref "D1") (pin "2") (pinfunction "A_2") (pintype "bidirectional"))
      (node (ref "L1") (pin "2") (pinfunction "2_2") (pintype "bidirectional"))
      (node (ref "R1") (pin "1") (pinfunction "1_1") (pintype "passive"))
    )
    (net (code "29") (name "/EXT_VIN_SW") (class "Default")
      (node (ref "C1") (pin "2") (pinfunction "2_2") (pintype "passive"))
      (node (ref "D3") (pin "1") (pinfunction "K_1") (pintype "bidirectional"))
      (node (ref "IC2") (pin "6") (pinfunction "SW_6") (pintype "bidirectional"))
      (node (ref "L1") (pin "1") (pinfunction "1_1") (pintype "bidirectional"))
    )
    (net (code "30") (name "/P6_ADC") (class "Default")
      (node (ref "JP6") (pin "2") (pinfunction "2_2") (pintype "passive"))
      (node (ref "R5") (pin "2") (pinfunction "2_2") (pintype "passive"))
    )
    (net (code "31") (name "/P6_ADC_INT") (class "Default")
      (node (ref "J1") (pin "7") (pintype "passive"))
      (node (ref "JP6") (pin "1") (pinfunction "1_1") (pintype "passive"))
    )
    (net (code "32") (name "/P10_FSYNC") (class "Default")
      (node (ref "D8") (pin "1") (pinfunction "1_1") (pintype "bidirectional"))
      (node (ref "IC4") (pin "4") (pinfunction "Y_4") (pintype "bidirectional"))
      (node (ref "JP7") (pin "2") (pinfunction "2_2") (pintype "passive"))
      (node (ref "R7") (pin "2") (pinfunction "2_2") (pintype "passive"))
      (node (ref "U1") (pin "2") (pinfunction "A_2") (pintype "bidirectional"))
    )
    (net (code "33") (name "/P10_FSYNC_INT") (class "Default")
      (node (ref "J6") (pin "3") (pintype "passive"))
      (node (ref "JP7") (pin "1") (pinfunction "1_1") (pintype "passive"))
    )
    (net (code "34") (name "/RS232_RXI") (class "Default")
      (node (ref "D14") (pin "1") (pinfunction "1_1") (pintype "bidirectional"))
      (node (ref "IC5") (pin "9") (pinfunction "ROUT_9") (pintype "bidirectional"))
      (node (ref "JP5") (pin "2") (pinfunction "2_2") (pintype "passive"))
      (node (ref "R15") (pin "2") (pinfunction "2_2") (pintype "passive"))
    )
    (net (code "35") (name "/RS232_RXI_INT") (class "Default")
      (node (ref "J1") (pin "6") (pintype "passive"))
      (node (ref "JP5") (pin "1") (pinfunction "1_1") (pintype "passive"))
    )
    (net (code "36") (name "/RS232_TXO") (class "Default")
      (node (ref "D13") (pin "1") (pinfunction "1_1") (pintype "bidirectional"))
      (node (ref "IC5") (pin "11") (pinfunction "DIN_11") (pintype "bidirectional"))
      (node (ref "JP4") (pin "2") (pinfunction "2_2") (pintype "passive"))
      (node (ref "R14") (pin "2") (pinfunction "2_2") (pintype "passive"))
    )
    (net (code "37") (name "/RS232_TXO_INT") (class "Default")
      (node (ref "J1") (pin "5") (pintype "passive"))
      (node (ref "JP4") (pin "1") (pinfunction "1_1") (pintype "passive"))
    )
    (net (code "38") (name "/RXI") (class "Default")
      (node (ref "IC5") (pin "8") (pinfunction "RIN_8") (pintype "bidirectional"))
      (node (ref "L5") (pin "1") (pinfunction "1_1") (pintype "passive"))
    )
    (net (code "39") (name "/SW") (class "Default")
      (node (ref "IC1") (pin "1") (pinfunction "SW_1") (pintype "bidirectional"))
      (node (ref "L2") (pin "2") (pinfunction "2_2") (pintype "passive"))
    )
    (net (code "40") (name "/SYNC") (class "Default")
      (node (ref "J2") (pin "8") (pinfunction "8_8") (pintype "bidirectional"))
      (node (ref "JP9") (pin "2") (pinfunction "2_2") (pintype "passive"))
    )
    (net (code "41") (name "/SYNC_IN") (class "Default")
      (node (ref "JP9") (pin "3") (pinfunction "3_3") (pintype "passive"))
      (node (ref "R10") (pin "2") (pinfunction "2_2") (pintype "passive"))
    )
    (net (code "42") (name "/SYNC_IN_INT") (class "Default")
      (node (ref "D7") (pin "1") (pinfunction "1_1") (pintype "bidirectional"))
      (node (ref "IC4") (pin "2") (pinfunction "A_2") (pintype "bidirectional"))
      (node (ref "R10") (pin "1") (pinfunction "1_1") (pintype "passive"))
      (node (ref "R6") (pin "2") (pinfunction "2_2") (pintype "passive"))
      (node (ref "Z3") (pin "1") (pinfunction "K_1") (pintype "bidirectional"))
    )
    (net (code "43") (name "/SYNC_OUT") (class "Default")
      (node (ref "JP9") (pin "1") (pinfunction "1_1") (pintype "passive"))
      (node (ref "R9") (pin "2") (pinfunction "2_2") (pintype "passive"))
    )
    (net (code "44") (name "/SYNC_OUT_INT") (class "Default")
      (node (ref "D9") (pin "1") (pinfunction "1_1") (pintype "bidirectional"))
      (node (ref "R9") (pin "1") (pinfunction "1_1") (pintype "passive"))
      (node (ref "U1") (pin "4") (pinfunction "Y_4") (pintype "bidirectional"))
    )
    (net (code "45") (name "/TXO") (class "Default")
      (node (ref "IC5") (pin "13") (pinfunction "DOUT_13") (pintype "bidirectional"))
      (node (ref "L3") (pin "1") (pinfunction "1_1") (pintype "passive"))
    )
    (net (code "46") (name "/V+") (class "Default")
      (node (ref "C22") (pin "1") (pinfunction "1_1") (pintype "passive"))
      (node (ref "IC5") (pin "3") (pinfunction "V+_3") (pintype "bidirectional"))
    )
    (net (code "47") (name "/V-") (class "Default")
      (node (ref "C21") (pin "1") (pinfunction "1_1") (pintype "passive"))
      (node (ref "IC5") (pin "7") (pinfunction "V-_7") (pintype "bidirectional"))
    )
    (net (code "48") (name "GND") (class "Default")
      (node (ref "C10") (pin "1") (pinfunction "1_1") (pintype "passive"))
      (node (ref "C11") (pin "1") (pinfunction "1_1") (pintype "passive"))
      (node (ref "C12") (pin "1") (pinfunction "1_1") (pintype "passive"))
      (node (ref "C13") (pin "1") (pinfunction "1_1") (pintype "passive"))
      (node (ref "C15") (pin "2") (pinfunction "2_2") (pintype "passive"))
      (node (ref "C17") (pin "2") (pinfunction "2_2") (pintype "passive"))
      (node (ref "C18") (pin "2") (pinfunction "2_2") (pintype "passive"))
      (node (ref "C19") (pin "2") (pinfunction "2_2") (pintype "passive"))
      (node (ref "C20") (pin "2") (pinfunction "2_2") (pintype "passive"))
      (node (ref "C21") (pin "2") (pinfunction "2_2") (pintype "passive"))
      (node (ref "C22") (pin "2") (pinfunction "2_2") (pintype "passive"))
      (node (ref "C23") (pin "2") (pinfunction "2_2") (pintype "passive"))
      (node (ref "C3") (pin "1") (pinfunction "1_1") (pintype "passive"))
      (node (ref "C4") (pin "1") (pinfunction "1_1") (pintype "passive"))
      (node (ref "C5") (pin "2") (pinfunction "2_2") (pintype "passive"))
      (node (ref "C6") (pin "1") (pinfunction "1_1") (pintype "passive"))
      (node (ref "C7") (pin "1") (pinfunction "1_1") (pintype "passive"))
      (node (ref "C8") (pin "1") (pinfunction "1_1") (pintype "passive"))
      (node (ref "C9") (pin "1") (pinfunction "1_1") (pintype "passive"))
      (node (ref "D10") (pin "2") (pinfunction "2_2") (pintype "bidirectional"))
      (node (ref "D11") (pin "2") (pinfunction "2_2") (pintype "bidirectional"))
      (node (ref "D12") (pin "3") (pinfunction "3_3") (pintype "bidirectional"))
      (node (ref "D13") (pin "2") (pinfunction "2_2") (pintype "bidirectional"))
      (node (ref "D14") (pin "2") (pinfunction "2_2") (pintype "bidirectional"))
      (node (ref "D15") (pin "3") (pinfunction "3_3") (pintype "bidirectional"))
      (node (ref "D2") (pin "2") (pinfunction "2_2") (pintype "bidirectional"))
      (node (ref "D3") (pin "2") (pinfunction "A_2") (pintype "bidirectional"))
      (node (ref "D4") (pin "1") (pinfunction "1_1") (pintype "bidirectional"))
      (node (ref "D5") (pin "2") (pinfunction "2_2") (pintype "bidirectional"))
      (node (ref "D6") (pin "2") (pinfunction "2_2") (pintype "bidirectional"))
      (node (ref "D7") (pin "2") (pinfunction "2_2") (pintype "bidirectional"))
      (node (ref "D8") (pin "2") (pinfunction "2_2") (pintype "bidirectional"))
      (node (ref "D9") (pin "2") (pinfunction "2_2") (pintype "bidirectional"))
      (node (ref "IC1") (pin "2") (pinfunction "GND_2") (pintype "bidirectional"))
      (node (ref "IC2") (pin "2") (pinfunction "GND_2") (pintype "bidirectional"))
      (node (ref "IC3") (pin "2") (pinfunction "V-_2") (pintype "input"))
      (node (ref "IC4") (pin "3") (pinfunction "GND_3") (pintype "bidirectional"))
      (node (ref "IC5") (pin "1") (pinfunction "~{EN}_1") (pintype "bidirectional"))
      (node (ref "IC5") (pin "14") (pinfunction "GND_14") (pintype "bidirectional"))
      (node (ref "IC6") (pin "2") (pinfunction "VSS_2") (pintype "bidirectional"))
      (node (ref "IC6") (pin "8") (pinfunction "STBY_8") (pintype "bidirectional"))
      (node (ref "J2") (pin "2") (pinfunction "2_2") (pintype "bidirectional"))
      (node (ref "J4") (pin "8") (pintype "passive"))
      (node (ref "J6") (pin "8") (pintype "passive"))
      (node (ref "R11") (pin "1") (pinfunction "1_1") (pintype "passive"))
      (node (ref "R2") (pin "2") (pinfunction "2_2") (pintype "passive"))
      (node (ref "R3") (pin "2") (pinfunction "2_2") (pintype "passive"))
      (node (ref "R8") (pin "2") (pinfunction "2_2") (pintype "passive"))
      (node (ref "U1") (pin "3") (pinfunction "GND_3") (pintype "bidirectional"))
      (node (ref "Z2") (pin "1") (pintype "passive"))
      (node (ref "Z3") (pin "2") (pinfunction "A_2") (pintype "bidirectional"))
    )
    (net (code "49") (name "VCC") (class "Default")
      (node (ref "C10") (pin "2") (pinfunction "2_2") (pintype "passive"))
      (node (ref "C18") (pin "1") (pinfunction "1_1") (pintype "passive"))
      (node (ref "C20") (pin "1") (pinfunction "1_1") (pintype "passive"))
      (node (ref "C3") (pin "2") (pinfunction "2_2") (pintype "passive"))
      (node (ref "D2") (pin "1") (pinfunction "1_1") (pintype "bidirectional"))
      (node (ref "IC4") (pin "5") (pinfunction "VCC_5") (pintype "bidirectional"))
      (node (ref "IC5") (pin "12") (pinfunction "FORCEON_12") (pintype "bidirectional"))
      (node (ref "IC5") (pin "15") (pinfunction "VCC_15") (pintype "bidirectional"))
      (node (ref "IC5") (pin "16") (pinfunction "~{FORCEOFF}_16") (pintype "bidirectional"))
      (node (ref "IC6") (pin "5") (pinfunction "VIO_5") (pintype "bidirectional"))
      (node (ref "J1") (pin "8") (pintype "passive"))
      (node (ref "J3") (pin "8") (pintype "passive"))
      (node (ref "L2") (pin "1") (pinfunction "1_1") (pintype "passive"))
      (node (ref "R12") (pin "1") (pinfunction "1_1") (pintype "passive"))
      (node (ref "R13") (pin "1") (pinfunction "1_1") (pintype "passive"))
      (node (ref "R14") (pin "1") (pinfunction "1_1") (pintype "passive"))
      (node (ref "R15") (pin "1") (pinfunction "1_1") (pintype "passive"))
      (node (ref "R7") (pin "1") (pinfunction "1_1") (pintype "passive"))
      (node (ref "Z2") (pin "2") (pintype "passive"))
    )
    (net (code "50") (name "VIN") (class "Default")
      (node (ref "D1") (pin "1") (pinfunction "K_1") (pintype "bidirectional"))
      (node (ref "J6") (pin "7") (pintype "passive"))
    )
    (net (code "51") (name "V_BATT") (class "Default")
      (node (ref "C11") (pin "2") (pinfunction "2_2") (pintype "passive"))
      (node (ref "C17") (pin "1") (pinfunction "1_1") (pintype "passive"))
      (node (ref "C4") (pin "2") (pinfunction "2_2") (pintype "passive"))
      (node (ref "C9") (pin "2") (pinfunction "2_2") (pintype "passive"))
      (node (ref "IC1") (pin "4") (pinfunction "VOUT_4") (pintype "bidirectional"))
      (node (ref "IC3") (pin "5") (pinfunction "V+_5") (pintype "input"))
      (node (ref "IC6") (pin "3") (pinfunction "VDD_3") (pintype "bidirectional"))
      (node (ref "R6") (pin "1") (pinfunction "1_1") (pintype "passive"))
      (node (ref "U1") (pin "5") (pinfunction "VCC_5") (pintype "bidirectional"))
    )
    (net (code "52") (name "unconnected-(IC1-NC_1-Pad3)") (class "Default")
      (node (ref "IC1") (pin "3") (pinfunction "NC_1_3") (pintype "bidirectional"))
    )
    (net (code "53") (name "unconnected-(IC1-NC_2-Pad5)") (class "Default")
      (node (ref "IC1") (pin "5") (pinfunction "NC_2_5") (pintype "bidirectional"))
    )
    (net (code "54") (name "unconnected-(IC4-N.C.-Pad1)") (class "Default")
      (node (ref "IC4") (pin "1") (pinfunction "N.C._1") (pintype "passive"))
    )
    (net (code "55") (name "unconnected-(IC5-~{INVALID}-Pad10)") (class "Default")
      (node (ref "IC5") (pin "10") (pinfunction "~{INVALID}_10") (pintype "bidirectional"))
    )
    (net (code "56") (name "unconnected-(J1-Pad1)") (class "Default")
      (node (ref "J1") (pin "1") (pintype "passive"))
    )
    (net (code "57") (name "unconnected-(J3-Pad1)") (class "Default")
      (node (ref "J3") (pin "1") (pintype "passive"))
    )
    (net (code "58") (name "unconnected-(J3-Pad2)") (class "Default")
      (node (ref "J3") (pin "2") (pintype "passive"))
    )
    (net (code "59") (name "unconnected-(J3-Pad3)") (class "Default")
      (node (ref "J3") (pin "3") (pintype "passive"))
    )
    (net (code "60") (name "unconnected-(J3-Pad4)") (class "Default")
      (node (ref "J3") (pin "4") (pintype "passive"))
    )
    (net (code "61") (name "unconnected-(J3-Pad5)") (class "Default")
      (node (ref "J3") (pin "5") (pintype "passive"))
    )
    (net (code "62") (name "unconnected-(J3-Pad6)") (class "Default")
      (node (ref "J3") (pin "6") (pintype "passive"))
    )
    (net (code "63") (name "unconnected-(J3-Pad7)") (class "Default")
      (node (ref "J3") (pin "7") (pintype "passive"))
    )
    (net (code "64") (name "unconnected-(J4-Pad1)") (class "Default")
      (node (ref "J4") (pin "1") (pintype "passive"))
    )
    (net (code "65") (name "unconnected-(J4-Pad2)") (class "Default")
      (node (ref "J4") (pin "2") (pintype "passive"))
    )
    (net (code "66") (name "unconnected-(J4-Pad3)") (class "Default")
      (node (ref "J4") (pin "3") (pintype "passive"))
    )
    (net (code "67") (name "unconnected-(J4-Pad4)") (class "Default")
      (node (ref "J4") (pin "4") (pintype "passive"))
    )
    (net (code "68") (name "unconnected-(J4-Pad5)") (class "Default")
      (node (ref "J4") (pin "5") (pintype "passive"))
    )
    (net (code "69") (name "unconnected-(J4-Pad6)") (class "Default")
      (node (ref "J4") (pin "6") (pintype "passive"))
    )
    (net (code "70") (name "unconnected-(J4-Pad7)") (class "Default")
      (node (ref "J4") (pin "7") (pintype "passive"))
    )
    (net (code "71") (name "unconnected-(J6-Pad1)") (class "Default")
      (node (ref "J6") (pin "1") (pintype "passive"))
    )
    (net (code "72") (name "unconnected-(J6-Pad2)") (class "Default")
      (node (ref "J6") (pin "2") (pintype "passive"))
    )
    (net (code "73") (name "unconnected-(J6-Pad4)") (class "Default")
      (node (ref "J6") (pin "4") (pintype "passive"))
    )
    (net (code "74") (name "unconnected-(J6-Pad5)") (class "Default")
      (node (ref "J6") (pin "5") (pintype "passive"))
    )
    (net (code "75") (name "unconnected-(J6-Pad6)") (class "Default")
      (node (ref "J6") (pin "6") (pintype "passive"))
    )
    (net (code "76") (name "unconnected-(U1-NC-Pad1)") (class "Default")
      (node (ref "U1") (pin "1") (pinfunction "NC_1") (pintype "passive"))
    )
  )
)
